# Final_eagle.net
KiCad netlist of a schematic drawn in EAGLE
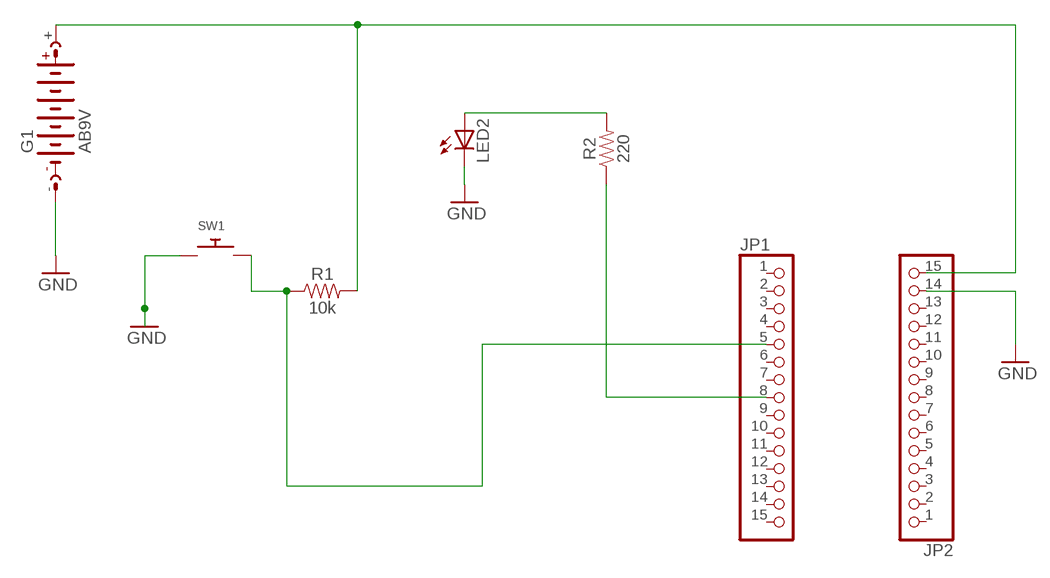
[diagram p0: schematic, sheet 1]

(export (version "E")
  (design (tool "Eeschema 10.0.6"))
  (components
    (comp (ref "G1")
      (value "AB9V")
      (footprint "eagle-import:AB9V")
      (libsource (lib "eagle-import") (part "AB9V"))
    )
    (comp (ref "JP1")
      (value "PINHD-1X15")
      (footprint "eagle-import:1X15")
      (libsource (lib "eagle-import") (part "PINHD-1X15"))
    )
    (comp (ref "JP2")
      (value "PINHD-1X15")
      (footprint "eagle-import:1X15")
      (libsource (lib "eagle-import") (part "PINHD-1X15"))
    )
    (comp (ref "LED2")
      (value "LED5MM")
      (footprint "eagle-import:LED5MM")
      (libsource (lib "eagle-import") (part "LED5MM"))
    )
    (comp (ref "R1")
      (value "10k")
      (footprint "eagle-import:AXIAL-0.1")
      (libsource (lib "eagle-import") (part "10KOHM-VERT-1/4W-5%"))
    )
    (comp (ref "R2")
      (value "220")
      (footprint "eagle-import:0603")
      (libsource (lib "eagle-import") (part "100OHM-0603-1/4W-5%"))
    )
    (comp (ref "SW1")
      (value "SWITCH_PUSHBUTTONEVQ-PE")
      (footprint "eagle-import:TACT_PANA-EVQ")
      (libsource (lib "eagle-import") (part "SWITCH_PUSHBUTTONEVQ-PE"))
    )
  )
  (nets
    (net (code "1") (name "GND") (class "Default")
      (node (ref "G1") (pin "-") (pinfunction "-_-") (pintype "passive"))
      (node (ref "JP2") (pin "14") (pinfunction "14_14") (pintype "passive"))
      (node (ref "LED2") (pin "K") (pinfunction "C_K") (pintype "passive"))
      (node (ref "SW1") (pin "P$1") (pinfunction "P$1_P$1") (pintype "passive"))
    )
    (net (code "2") (name "Net-(JP1-Pad8)") (class "Default")
      (node (ref "JP1") (pin "8") (pinfunction "8_8") (pintype "passive"))
      (node (ref "R2") (pin "1") (pinfunction "1_1") (pintype "passive"))
    )
    (net (code "3") (name "Net-(LED2-PadA)") (class "Default")
      (node (ref "LED2") (pin "A") (pinfunction "A_A") (pintype "passive"))
      (node (ref "R2") (pin "2") (pinfunction "2_2") (pintype "passive"))
    )
    (net (code "4") (name "Net-(R1-1)") (class "Default")
      (node (ref "JP1") (pin "5") (pinfunction "5_5") (pintype "passive"))
      (node (ref "R1") (pin "P$1") (pinfunction "1_P$1") (pintype "passive"))
      (node (ref "SW1") (pin "P$2") (pinfunction "P$2_P$2") (pintype "passive"))
    )
    (net (code "5") (name "Net-(R1-2)") (class "Default")
      (node (ref "G1") (pin "+") (pinfunction "+_+") (pintype "passive"))
      (node (ref "JP2") (pin "15") (pinfunction "15_15") (pintype "passive"))
      (node (ref "R1") (pin "P$2") (pinfunction "2_P$2") (pintype "passive"))
    )
    (net (code "6") (name "unconnected-(JP1-Pad1)") (class "Default")
      (node (ref "JP1") (pin "1") (pinfunction "1_1") (pintype "passive"))
    )
    (net (code "7") (name "unconnected-(JP1-Pad2)") (class "Default")
      (node (ref "JP1") (pin "2") (pinfunction "2_2") (pintype "passive"))
    )
    (net (code "8") (name "unconnected-(JP1-Pad3)") (class "Default")
      (node (ref "JP1") (pin "3") (pinfunction "3_3") (pintype "passive"))
    )
    (net (code "9") (name "unconnected-(JP1-Pad4)") (class "Default")
      (node (ref "JP1") (pin "4") (pinfunction "4_4") (pintype "passive"))
    )
    (net (code "10") (name "unconnected-(JP1-Pad6)") (class "Default")
      (node (ref "JP1") (pin "6") (pinfunction "6_6") (pintype "passive"))
    )
    (net (code "11") (name "unconnected-(JP1-Pad7)") (class "Default")
      (node (ref "JP1") (pin "7") (pinfunction "7_7") (pintype "passive"))
    )
    (net (code "12") (name "unconnected-(JP1-Pad9)") (class "Default")
      (node (ref "JP1") (pin "9") (pinfunction "9_9") (pintype "passive"))
    )
    (net (code "13") (name "unconnected-(JP1-Pad10)") (class "Default")
      (node (ref "JP1") (pin "10") (pinfunction "10_10") (pintype "passive"))
    )
    (net (code "14") (name "unconnected-(JP1-Pad11)") (class "Default")
      (node (ref "JP1") (pin "11") (pinfunction "11_11") (pintype "passive"))
    )
    (net (code "15") (name "unconnected-(JP1-Pad12)") (class "Default")
      (node (ref "JP1") (pin "12") (pinfunction "12_12") (pintype "passive"))
    )
    (net (code "16") (name "unconnected-(JP1-Pad13)") (class "Default")
      (node (ref "JP1") (pin "13") (pinfunction "13_13") (pintype "passive"))
    )
    (net (code "17") (name "unconnected-(JP1-Pad14)") (class "Default")
      (node (ref "JP1") (pin "14") (pinfunction "14_14") (pintype "passive"))
    )
    (net (code "18") (name "unconnected-(JP1-Pad15)") (class "Default")
      (node (ref "JP1") (pin "15") (pinfunction "15_15") (pintype "passive"))
    )
    (net (code "19") (name "unconnected-(JP2-Pad1)") (class "Default")
      (node (ref "JP2") (pin "1") (pinfunction "1_1") (pintype "passive"))
    )
    (net (code "20") (name "unconnected-(JP2-Pad2)") (class "Default")
      (node (ref "JP2") (pin "2") (pinfunction "2_2") (pintype "passive"))
    )
    (net (code "21") (name "unconnected-(JP2-Pad3)") (class "Default")
      (node (ref "JP2") (pin "3") (pinfunction "3_3") (pintype "passive"))
    )
    (net (code "22") (name "unconnected-(JP2-Pad4)") (class "Default")
      (node (ref "JP2") (pin "4") (pinfunction "4_4") (pintype "passive"))
    )
    (net (code "23") (name "unconnected-(JP2-Pad5)") (class "Default")
      (node (ref "JP2") (pin "5") (pinfunction "5_5") (pintype "passive"))
    )
    (net (code "24") (name "unconnected-(JP2-Pad6)") (class "Default")
      (node (ref "JP2") (pin "6") (pinfunction "6_6") (pintype "passive"))
    )
    (net (code "25") (name "unconnected-(JP2-Pad7)") (class "Default")
      (node (ref "JP2") (pin "7") (pinfunction "7_7") (pintype "passive"))
    )
    (net (code "26") (name "unconnected-(JP2-Pad8)") (class "Default")
      (node (ref "JP2") (pin "8") (pinfunction "8_8") (pintype "passive"))
    )
    (net (code "27") (name "unconnected-(JP2-Pad9)") (class "Default")
      (node (ref "JP2") (pin "9") (pinfunction "9_9") (pintype "passive"))
    )
    (net (code "28") (name "unconnected-(JP2-Pad10)") (class "Default")
      (node (ref "JP2") (pin "10") (pinfunction "10_10") (pintype "passive"))
    )
    (net (code "29") (name "unconnected-(JP2-Pad11)") (class "Default")
      (node (ref "JP2") (pin "11") (pinfunction "11_11") (pintype "passive"))
    )
    (net (code "30") (name "unconnected-(JP2-Pad12)") (class "Default")
      (node (ref "JP2") (pin "12") (pinfunction "12_12") (pintype "passive"))
    )
    (net (code "31") (name "unconnected-(JP2-Pad13)") (class "Default")
      (node (ref "JP2") (pin "13") (pinfunction "13_13") (pintype "passive"))
    )
  )
)
